# generator_36KHz.net
KiCad netlist of a schematic drawn in EAGLE
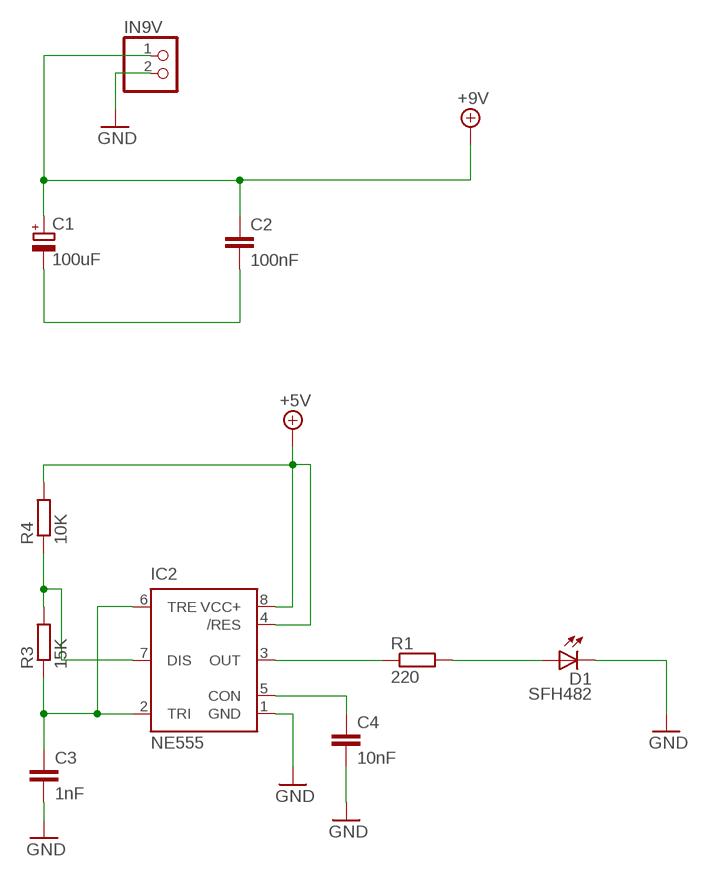
[diagram p0: schematic, sheet 1]

(export (version "E")
  (design (tool "Eeschema 10.0.6"))
  (components
    (comp (ref "C1")
      (value "100uF")
      (footprint "eagle-import:EB22,5D")
      (libsource (lib "eagle-import") (part "CPOL-EUE10-22.5"))
    )
    (comp (ref "C2")
      (value "100nF")
      (footprint "eagle-import:C2.5-3")
      (libsource (lib "eagle-import") (part "C2,5-3"))
    )
    (comp (ref "C3")
      (value "1nF")
      (footprint "eagle-import:C2.5-3")
      (libsource (lib "eagle-import") (part "C2,5-3"))
    )
    (comp (ref "C4")
      (value "10nF")
      (footprint "eagle-import:C2.5-3")
      (libsource (lib "eagle-import") (part "C2,5-3"))
    )
    (comp (ref "D1")
      (value "SFH482")
      (footprint "eagle-import:SFH482")
      (libsource (lib "eagle-import") (part "SFH482"))
    )
    (comp (ref "IC2")
      (value "NE555")
      (footprint "eagle-import:DIL-08")
      (fields (field (name "MF") "Arrow Electronics") (field (name "MPN") "NE555N"))
      (libsource (lib "eagle-import") (part "NE555"))
    )
    (comp (ref "IN9V")
      (value "PINHD-1X2")
      (footprint "eagle-import:1X02")
      (libsource (lib "eagle-import") (part "PINHD-1X2"))
    )
    (comp (ref "R1")
      (value "220")
      (footprint "eagle-import:0207_5V")
      (libsource (lib "eagle-import") (part "R-EU_0207/5V"))
    )
    (comp (ref "R3")
      (value "15K")
      (footprint "eagle-import:0207_5V")
      (libsource (lib "eagle-import") (part "R-EU_0207/5V"))
    )
    (comp (ref "R4")
      (value "10K")
      (footprint "eagle-import:0207_5V")
      (libsource (lib "eagle-import") (part "R-EU_0207/5V"))
    )
  )
  (nets
    (net (code "1") (name "+5V") (class "Default")
      (node (ref "IC2") (pin "4") (pinfunction "/RES_4") (pintype "input"))
      (node (ref "IC2") (pin "8") (pinfunction "VCC+_8") (pintype "power_in"))
      (node (ref "R4") (pin "2") (pinfunction "2_2") (pintype "passive"))
    )
    (net (code "2") (name "+9V") (class "Default")
      (node (ref "C1") (pin "+") (pinfunction "+_+") (pintype "passive"))
      (node (ref "C2") (pin "1") (pinfunction "1_1") (pintype "passive"))
      (node (ref "IN9V") (pin "1") (pinfunction "1_1") (pintype "passive"))
    )
    (net (code "3") (name "GND") (class "Default")
      (node (ref "C3") (pin "2") (pinfunction "2_2") (pintype "passive"))
      (node (ref "C4") (pin "2") (pinfunction "2_2") (pintype "passive"))
      (node (ref "D1") (pin "K") (pinfunction "C_K") (pintype "passive"))
      (node (ref "IC2") (pin "1") (pinfunction "GND_1") (pintype "power_in"))
      (node (ref "IN9V") (pin "2") (pinfunction "2_2") (pintype "passive"))
    )
    (net (code "4") (name "Net-(C1-Pad-)") (class "Default")
      (node (ref "C1") (pin "-") (pinfunction "-_-") (pintype "passive"))
      (node (ref "C2") (pin "2") (pinfunction "2_2") (pintype "passive"))
    )
    (net (code "5") (name "Net-(D1-PadA)") (class "Default")
      (node (ref "D1") (pin "A") (pinfunction "A_A") (pintype "passive"))
      (node (ref "R1") (pin "2") (pinfunction "2_2") (pintype "passive"))
    )
    (net (code "6") (name "Net-(IC2-CON)") (class "Default")
      (node (ref "C4") (pin "1") (pinfunction "1_1") (pintype "passive"))
      (node (ref "IC2") (pin "5") (pinfunction "CON_5") (pintype "input"))
    )
    (net (code "7") (name "Net-(IC2-DIS)") (class "Default")
      (node (ref "IC2") (pin "7") (pinfunction "DIS_7") (pintype "input"))
      (node (ref "R3") (pin "2") (pinfunction "2_2") (pintype "passive"))
      (node (ref "R4") (pin "1") (pinfunction "1_1") (pintype "passive"))
    )
    (net (code "8") (name "Net-(IC2-OUT)") (class "Default")
      (node (ref "IC2") (pin "3") (pinfunction "OUT_3") (pintype "output"))
      (node (ref "R1") (pin "1") (pinfunction "1_1") (pintype "passive"))
    )
    (net (code "9") (name "Net-(IC2-TRE)") (class "Default")
      (node (ref "C3") (pin "1") (pinfunction "1_1") (pintype "passive"))
      (node (ref "IC2") (pin "2") (pinfunction "TRI_2") (pintype "input"))
      (node (ref "IC2") (pin "6") (pinfunction "TRE_6") (pintype "input"))
      (node (ref "R3") (pin "1") (pinfunction "1_1") (pintype "passive"))
    )
  )
)
